# relays.net
KiCad netlist of a schematic drawn in Altium Designer
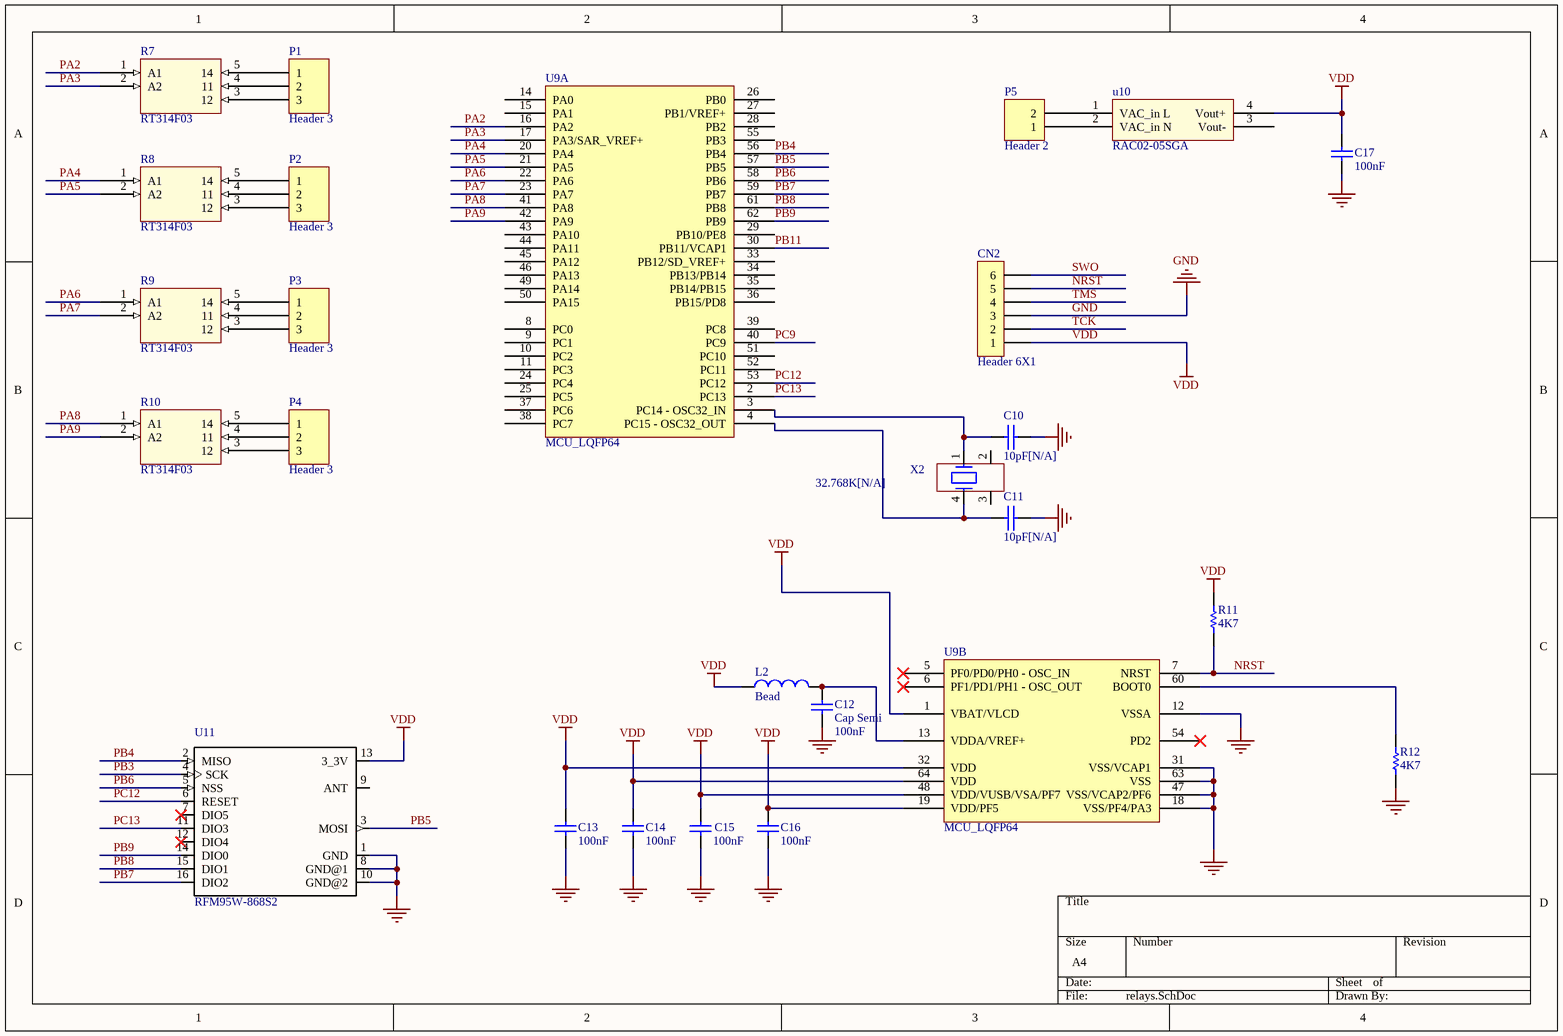
[diagram p0: relays.SchDoc]

(export (version "E")
  (design (tool "Eeschema 10.0.6"))
  (components
    (comp (ref "C10")
      (value "10pF[N/A]")
      (footprint "0603C")
      (description "Capacitor")
      (libsource (lib "MB1136") (part "CAP"))
    )
    (comp (ref "C11")
      (value "10pF[N/A]")
      (footprint "0603C")
      (description "Capacitor")
      (libsource (lib "*") (part "CAP"))
    )
    (comp (ref "C12")
      (value "Cap Semi")
      (footprint "1608[0603]")
      (description "Capacitor (Semiconductor SIM Model)")
      (fields (field (name "ALTIUM_VALUE") "100nF") (field (name "PUBLISHER") "Altium Limited"))
      (libsource (lib "Miscellaneous Devices") (part "Cap Semi"))
    )
    (comp (ref "C13")
      (value "100nF")
      (footprint "0603C")
      (description "Capacitor")
      (fields (field (name "PUBLISHER") "Altium Limited"))
      (libsource (lib "Miscellaneous Devices") (part "Cap"))
    )
    (comp (ref "C14")
      (value "100nF")
      (footprint "0603C")
      (description "Capacitor")
      (fields (field (name "PUBLISHER") "Altium Limited"))
      (libsource (lib "Miscellaneous Devices") (part "Cap"))
    )
    (comp (ref "C15")
      (value "100nF")
      (footprint "0603C")
      (description "Capacitor")
      (fields (field (name "PUBLISHER") "Altium Limited"))
      (libsource (lib "Miscellaneous Devices") (part "Cap"))
    )
    (comp (ref "C16")
      (value "100nF")
      (footprint "0603C")
      (description "Capacitor")
      (fields (field (name "PUBLISHER") "Altium Limited"))
      (libsource (lib "Miscellaneous Devices") (part "Cap"))
    )
    (comp (ref "C17")
      (value "100nF")
      (footprint "0603C")
      (description "Capacitor")
      (fields (field (name "PUBLISHER") "Altium Limited"))
      (libsource (lib "Miscellaneous Devices") (part "Cap"))
    )
    (comp (ref "CN2")
      (value "Header 6X1")
      (footprint "1*6P")
      (description "Header, 6-Pin, Single row")
      (fields (field (name "PUBLISHER") "Altium Limited"))
      (libsource (lib "MB1136") (part "Header 6X1"))
    )
    (comp (ref "L2")
      (value "Bead")
      (footprint "INDC1608L")
      (description "Inductor")
      (fields (field (name "PUBLISHER") "Altium Limited"))
      (libsource (lib "Miscellaneous Devices") (part "Inductor"))
    )
    (comp (ref "P1")
      (value "Header 3")
      (footprint "HDR1X3")
      (description "Header, 3-Pin")
      (fields (field (name "PUBLISHER") "Altium Limited"))
      (libsource (lib "Miscellaneous Connectors") (part "Header 3"))
    )
    (comp (ref "P2")
      (value "Header 3")
      (footprint "HDR1X3")
      (description "Header, 3-Pin")
      (fields (field (name "PUBLISHER") "Altium Limited"))
      (libsource (lib "Miscellaneous Connectors") (part "Header 3"))
    )
    (comp (ref "P3")
      (value "Header 3")
      (footprint "HDR1X3")
      (description "Header, 3-Pin")
      (fields (field (name "PUBLISHER") "Altium Limited"))
      (libsource (lib "Miscellaneous Connectors") (part "Header 3"))
    )
    (comp (ref "P4")
      (value "Header 3")
      (footprint "HDR1X3")
      (description "Header, 3-Pin")
      (fields (field (name "PUBLISHER") "Altium Limited"))
      (libsource (lib "Miscellaneous Connectors") (part "Header 3"))
    )
    (comp (ref "P5")
      (value "Header 2")
      (footprint "HDR1X2")
      (description "Header, 2-Pin")
      (fields (field (name "PUBLISHER") "Altium Limited"))
      (libsource (lib "Miscellaneous Connectors") (part "Header 2"))
    )
    (comp (ref "R7")
      (value "RT314F03")
      (footprint "RT314F03")
      (description "Latching relay")
      (libsource (lib "seeds") (part "RT314F03"))
    )
    (comp (ref "R8")
      (value "RT314F03")
      (footprint "RT314F03")
      (description "Latching relay")
      (libsource (lib "seeds") (part "RT314F03"))
    )
    (comp (ref "R9")
      (value "RT314F03")
      (footprint "RT314F03")
      (description "Latching relay")
      (libsource (lib "seeds") (part "RT314F03"))
    )
    (comp (ref "R10")
      (value "RT314F03")
      (footprint "RT314F03")
      (description "Latching relay")
      (libsource (lib "seeds") (part "RT314F03"))
    )
    (comp (ref "R11")
      (value "4K7")
      (footprint "0603R")
      (description "Resistor")
      (fields (field (name "PUBLISHER") "Altium Limited"))
      (libsource (lib "MB1136") (part "Res1"))
    )
    (comp (ref "R12")
      (value "4K7")
      (footprint "0603R")
      (description "Resistor")
      (fields (field (name "PUBLISHER") "Altium Limited"))
      (libsource (lib "MB1136") (part "Res1"))
    )
    (comp (ref "U9") (value "MCU_LQFP64") (footprint "LQFP64") (libsource (lib "MB1136") (part "MCU_LQFP64")))
    (comp (ref "u10")
      (value "RAC02-05SGA")
      (description "AC/DC converter")
      (libsource (lib "seeds") (part "RAC02-05SGA"))
    )
    (comp (ref "U11")
      (value "RFM95W-868S2")
      (footprint "XCVR_RFM95W-868S2")
      (fields (field (name "MF") "Hope Microelectronics"))
      (libsource (lib "RFM95W-868S2") (part "RFM95W-868S2"))
    )
    (comp (ref "X2") (value "32.768K[N/A]") (footprint "XTAL_4SM_8X3R8") (libsource (lib "*") (part "MC306")))
  )
  (nets
    (net (code "1") (name "/NRST") (class "Default")
      (node (ref "CN2") (pin "5") (pinfunction "5_5") (pintype "passive"))
      (node (ref "R11") (pin "1") (pinfunction "1_1") (pintype "passive"))
      (node (ref "U9") (pin "7") (pinfunction "NRST_7") (pintype "passive"))
    )
    (net (code "2") (name "/PA2") (class "Default")
      (node (ref "R7") (pin "1") (pinfunction "A1_1") (pintype "input"))
      (node (ref "U9") (pin "16") (pinfunction "PA2_16") (pintype "passive"))
    )
    (net (code "3") (name "/PA3") (class "Default")
      (node (ref "R7") (pin "2") (pinfunction "A2_2") (pintype "input"))
      (node (ref "U9") (pin "17") (pinfunction "PA3/SAR_VREF+_17") (pintype "passive"))
    )
    (net (code "4") (name "/PA4") (class "Default")
      (node (ref "R8") (pin "1") (pinfunction "A1_1") (pintype "input"))
      (node (ref "U9") (pin "20") (pinfunction "PA4_20") (pintype "passive"))
    )
    (net (code "5") (name "/PA5") (class "Default")
      (node (ref "R8") (pin "2") (pinfunction "A2_2") (pintype "input"))
      (node (ref "U9") (pin "21") (pinfunction "PA5_21") (pintype "passive"))
    )
    (net (code "6") (name "/PA6") (class "Default")
      (node (ref "R9") (pin "1") (pinfunction "A1_1") (pintype "input"))
      (node (ref "U9") (pin "22") (pinfunction "PA6_22") (pintype "passive"))
    )
    (net (code "7") (name "/PA7") (class "Default")
      (node (ref "R9") (pin "2") (pinfunction "A2_2") (pintype "input"))
      (node (ref "U9") (pin "23") (pinfunction "PA7_23") (pintype "passive"))
    )
    (net (code "8") (name "/PA8") (class "Default")
      (node (ref "R10") (pin "1") (pinfunction "A1_1") (pintype "input"))
      (node (ref "U9") (pin "41") (pinfunction "PA8_41") (pintype "passive"))
    )
    (net (code "9") (name "/PA9") (class "Default")
      (node (ref "R10") (pin "2") (pinfunction "A2_2") (pintype "input"))
      (node (ref "U9") (pin "42") (pinfunction "PA9_42") (pintype "passive"))
    )
    (net (code "10") (name "/PB3") (class "Default")
      (node (ref "U11") (pin "4") (pinfunction "SCK_4") (pintype "input"))
    )
    (net (code "11") (name "/PB4") (class "Default")
      (node (ref "U11") (pin "2") (pinfunction "MISO_2") (pintype "input"))
      (node (ref "U9") (pin "56") (pinfunction "PB4_56") (pintype "passive"))
    )
    (net (code "12") (name "/PB5") (class "Default")
      (node (ref "U11") (pin "3") (pinfunction "MOSI_3") (pintype "output"))
      (node (ref "U9") (pin "57") (pinfunction "PB5_57") (pintype "passive"))
    )
    (net (code "13") (name "/PB6") (class "Default")
      (node (ref "U11") (pin "5") (pinfunction "NSS_5") (pintype "input"))
      (node (ref "U9") (pin "58") (pinfunction "PB6_58") (pintype "passive"))
    )
    (net (code "14") (name "/PB7") (class "Default")
      (node (ref "U11") (pin "16") (pinfunction "DIO2_16") (pintype "bidirectional"))
      (node (ref "U9") (pin "59") (pinfunction "PB7_59") (pintype "passive"))
    )
    (net (code "15") (name "/PB8") (class "Default")
      (node (ref "U11") (pin "15") (pinfunction "DIO1_15") (pintype "bidirectional"))
      (node (ref "U9") (pin "61") (pinfunction "PB8_61") (pintype "passive"))
    )
    (net (code "16") (name "/PB9") (class "Default")
      (node (ref "U11") (pin "14") (pinfunction "DIO0_14") (pintype "bidirectional"))
      (node (ref "U9") (pin "62") (pinfunction "PB9_62") (pintype "passive"))
    )
    (net (code "17") (name "/PB11") (class "Default")
      (node (ref "U9") (pin "30") (pinfunction "PB11/VCAP1_30") (pintype "passive"))
    )
    (net (code "18") (name "/PC9") (class "Default")
      (node (ref "U9") (pin "40") (pinfunction "PC9_40") (pintype "passive"))
    )
    (net (code "19") (name "/PC12") (class "Default")
      (node (ref "U11") (pin "6") (pinfunction "RESET_6") (pintype "bidirectional"))
      (node (ref "U9") (pin "53") (pinfunction "PC12_53") (pintype "passive"))
    )
    (net (code "20") (name "/PC13") (class "Default")
      (node (ref "U11") (pin "11") (pinfunction "DIO3_11") (pintype "bidirectional"))
      (node (ref "U9") (pin "2") (pinfunction "PC13_2") (pintype "passive"))
    )
    (net (code "21") (name "/SWO") (class "Default")
      (node (ref "CN2") (pin "6") (pinfunction "6_6") (pintype "passive"))
    )
    (net (code "22") (name "/TCK") (class "Default")
      (node (ref "CN2") (pin "2") (pinfunction "2_2") (pintype "passive"))
    )
    (net (code "23") (name "/TMS") (class "Default")
      (node (ref "CN2") (pin "4") (pinfunction "4_4") (pintype "passive"))
    )
    (net (code "24") (name "GND") (class "Default")
      (node (ref "C10") (pin "2") (pinfunction "2_2") (pintype "passive"))
      (node (ref "C11") (pin "2") (pinfunction "2_2") (pintype "passive"))
      (node (ref "C12") (pin "2") (pinfunction "2_2") (pintype "passive"))
      (node (ref "C13") (pin "2") (pinfunction "2_2") (pintype "passive"))
      (node (ref "C14") (pin "2") (pinfunction "2_2") (pintype "passive"))
      (node (ref "C15") (pin "2") (pinfunction "2_2") (pintype "passive"))
      (node (ref "C16") (pin "2") (pinfunction "2_2") (pintype "passive"))
      (node (ref "C17") (pin "2") (pinfunction "2_2") (pintype "passive"))
      (node (ref "CN2") (pin "3") (pinfunction "3_3") (pintype "passive"))
      (node (ref "R12") (pin "1") (pinfunction "1_1") (pintype "passive"))
      (node (ref "U11") (pin "1") (pinfunction "GND_1") (pintype "power_in"))
      (node (ref "U11") (pin "10") (pinfunction "GND@2_10") (pintype "power_in"))
      (node (ref "U11") (pin "8") (pinfunction "GND@1_8") (pintype "power_in"))
      (node (ref "U9") (pin "12") (pinfunction "VSSA_12") (pintype "passive"))
      (node (ref "U9") (pin "18") (pinfunction "VSS/PF4/PA3_18") (pintype "passive"))
      (node (ref "U9") (pin "31") (pinfunction "VSS/VCAP1_31") (pintype "passive"))
      (node (ref "U9") (pin "47") (pinfunction "VSS/VCAP2/PF6_47") (pintype "passive"))
      (node (ref "U9") (pin "63") (pinfunction "VSS_63") (pintype "passive"))
    )
    (net (code "25") (name "Net-(R7-11)") (class "Default")
      (node (ref "P1") (pin "2") (pinfunction "2_2") (pintype "passive"))
      (node (ref "R7") (pin "4") (pinfunction "11_4") (pintype "input"))
    )
    (net (code "26") (name "Net-(R7-12)") (class "Default")
      (node (ref "P1") (pin "3") (pinfunction "3_3") (pintype "passive"))
      (node (ref "R7") (pin "3") (pinfunction "12_3") (pintype "input"))
    )
    (net (code "27") (name "Net-(R7-14)") (class "Default")
      (node (ref "P1") (pin "1") (pinfunction "1_1") (pintype "passive"))
      (node (ref "R7") (pin "5") (pinfunction "14_5") (pintype "input"))
    )
    (net (code "28") (name "Net-(R8-11)") (class "Default")
      (node (ref "P2") (pin "2") (pinfunction "2_2") (pintype "passive"))
      (node (ref "R8") (pin "4") (pinfunction "11_4") (pintype "input"))
    )
    (net (code "29") (name "Net-(R8-12)") (class "Default")
      (node (ref "P2") (pin "3") (pinfunction "3_3") (pintype "passive"))
      (node (ref "R8") (pin "3") (pinfunction "12_3") (pintype "input"))
    )
    (net (code "30") (name "Net-(R8-14)") (class "Default")
      (node (ref "P2") (pin "1") (pinfunction "1_1") (pintype "passive"))
      (node (ref "R8") (pin "5") (pinfunction "14_5") (pintype "input"))
    )
    (net (code "31") (name "Net-(R9-11)") (class "Default")
      (node (ref "P3") (pin "2") (pinfunction "2_2") (pintype "passive"))
      (node (ref "R9") (pin "4") (pinfunction "11_4") (pintype "input"))
    )
    (net (code "32") (name "Net-(R9-12)") (class "Default")
      (node (ref "P3") (pin "3") (pinfunction "3_3") (pintype "passive"))
      (node (ref "R9") (pin "3") (pinfunction "12_3") (pintype "input"))
    )
    (net (code "33") (name "Net-(R9-14)") (class "Default")
      (node (ref "P3") (pin "1") (pinfunction "1_1") (pintype "passive"))
      (node (ref "R9") (pin "5") (pinfunction "14_5") (pintype "input"))
    )
    (net (code "34") (name "Net-(R10-11)") (class "Default")
      (node (ref "P4") (pin "2") (pinfunction "2_2") (pintype "passive"))
      (node (ref "R10") (pin "4") (pinfunction "11_4") (pintype "input"))
    )
    (net (code "35") (name "Net-(R10-12)") (class "Default")
      (node (ref "P4") (pin "3") (pinfunction "3_3") (pintype "passive"))
      (node (ref "R10") (pin "3") (pinfunction "12_3") (pintype "input"))
    )
    (net (code "36") (name "Net-(R10-14)") (class "Default")
      (node (ref "P4") (pin "1") (pinfunction "1_1") (pintype "passive"))
      (node (ref "R10") (pin "5") (pinfunction "14_5") (pintype "input"))
    )
    (net (code "37") (name "Net-(U9A-PC14_-_OSC32_IN)") (class "Default")
      (node (ref "C10") (pin "1") (pinfunction "1_1") (pintype "passive"))
      (node (ref "U9") (pin "3") (pinfunction "PC14_-_OSC32_IN_3") (pintype "passive"))
      (node (ref "X2") (pin "1") (pinfunction "1_1") (pintype "passive"))
    )
    (net (code "38") (name "Net-(U9A-PC15_-_OSC32_OUT)") (class "Default")
      (node (ref "C11") (pin "1") (pinfunction "1_1") (pintype "passive"))
      (node (ref "U9") (pin "4") (pinfunction "PC15_-_OSC32_OUT_4") (pintype "passive"))
      (node (ref "X2") (pin "4") (pinfunction "4_4") (pintype "passive"))
    )
    (net (code "39") (name "Net-(U9B-BOOT0)") (class "Default")
      (node (ref "R12") (pin "2") (pinfunction "2_2") (pintype "passive"))
      (node (ref "U9") (pin "60") (pinfunction "BOOT0_60") (pintype "passive"))
    )
    (net (code "40") (name "Net-(U9B-VDDA{slash}VREF+)") (class "Default")
      (node (ref "C12") (pin "1") (pinfunction "1_1") (pintype "passive"))
      (node (ref "L2") (pin "2") (pinfunction "2_2") (pintype "passive"))
      (node (ref "U9") (pin "13") (pinfunction "VDDA/VREF+_13") (pintype "passive"))
    )
    (net (code "41") (name "Net-(u10-VAC_in_L)") (class "Default")
      (node (ref "P5") (pin "2") (pinfunction "2_2") (pintype "passive"))
      (node (ref "u10") (pin "1") (pinfunction "VAC_in_L_1") (pintype "power_in"))
    )
    (net (code "42") (name "Net-(u10-VAC_in_N)") (class "Default")
      (node (ref "P5") (pin "1") (pinfunction "1_1") (pintype "passive"))
      (node (ref "u10") (pin "2") (pinfunction "VAC_in_N_2") (pintype "power_in"))
    )
    (net (code "43") (name "VDD") (class "Default")
      (node (ref "C13") (pin "1") (pinfunction "1_1") (pintype "passive"))
      (node (ref "C14") (pin "1") (pinfunction "1_1") (pintype "passive"))
      (node (ref "C15") (pin "1") (pinfunction "1_1") (pintype "passive"))
      (node (ref "C16") (pin "1") (pinfunction "1_1") (pintype "passive"))
      (node (ref "C17") (pin "1") (pinfunction "1_1") (pintype "passive"))
      (node (ref "CN2") (pin "1") (pinfunction "1_1") (pintype "passive"))
      (node (ref "L2") (pin "1") (pinfunction "1_1") (pintype "passive"))
      (node (ref "R11") (pin "2") (pinfunction "2_2") (pintype "passive"))
      (node (ref "U11") (pin "13") (pinfunction "3_3V_13") (pintype "power_in"))
      (node (ref "U9") (pin "1") (pinfunction "VBAT/VLCD_1") (pintype "passive"))
      (node (ref "U9") (pin "19") (pinfunction "VDD/PF5_19") (pintype "passive"))
      (node (ref "U9") (pin "32") (pinfunction "VDD_32") (pintype "passive"))
      (node (ref "U9") (pin "48") (pinfunction "VDD/VUSB/VSA/PF7_48") (pintype "passive"))
      (node (ref "U9") (pin "64") (pinfunction "VDD_64") (pintype "passive"))
      (node (ref "u10") (pin "4") (pinfunction "Vout+_4") (pintype "power_in"))
    )
    (net (code "44") (name "unconnected-(U9A-PA0-Pad14)") (class "Default")
      (node (ref "U9") (pin "14") (pinfunction "PA0_14") (pintype "passive"))
    )
    (net (code "45") (name "unconnected-(U9A-PA1-Pad15)") (class "Default")
      (node (ref "U9") (pin "15") (pinfunction "PA1_15") (pintype "passive"))
    )
    (net (code "46") (name "unconnected-(U9A-PA10-Pad43)") (class "Default")
      (node (ref "U9") (pin "43") (pinfunction "PA10_43") (pintype "passive"))
    )
    (net (code "47") (name "unconnected-(U9A-PA11-Pad44)") (class "Default")
      (node (ref "U9") (pin "44") (pinfunction "PA11_44") (pintype "passive"))
    )
    (net (code "48") (name "unconnected-(U9A-PA12-Pad45)") (class "Default")
      (node (ref "U9") (pin "45") (pinfunction "PA12_45") (pintype "passive"))
    )
    (net (code "49") (name "unconnected-(U9A-PA13-Pad46)") (class "Default")
      (node (ref "U9") (pin "46") (pinfunction "PA13_46") (pintype "passive"))
    )
    (net (code "50") (name "unconnected-(U9A-PA14-Pad49)") (class "Default")
      (node (ref "U9") (pin "49") (pinfunction "PA14_49") (pintype "passive"))
    )
    (net (code "51") (name "unconnected-(U9A-PA15-Pad50)") (class "Default")
      (node (ref "U9") (pin "50") (pinfunction "PA15_50") (pintype "passive"))
    )
    (net (code "52") (name "unconnected-(U9A-PB0-Pad26)") (class "Default")
      (node (ref "U9") (pin "26") (pinfunction "PB0_26") (pintype "passive"))
    )
    (net (code "53") (name "unconnected-(U9A-PB1{slash}VREF+-Pad27)") (class "Default")
      (node (ref "U9") (pin "27") (pinfunction "PB1/VREF+_27") (pintype "passive"))
    )
    (net (code "54") (name "unconnected-(U9A-PB2-Pad28)") (class "Default")
      (node (ref "U9") (pin "28") (pinfunction "PB2_28") (pintype "passive"))
    )
    (net (code "55") (name "unconnected-(U9A-PB3-Pad55)") (class "Default")
      (node (ref "U9") (pin "55") (pinfunction "PB3_55") (pintype "passive"))
    )
    (net (code "56") (name "unconnected-(U9A-PB10{slash}PE8-Pad29)") (class "Default")
      (node (ref "U9") (pin "29") (pinfunction "PB10/PE8_29") (pintype "passive"))
    )
    (net (code "57") (name "unconnected-(U9A-PB12{slash}SD_VREF+-Pad33)") (class "Default")
      (node (ref "U9") (pin "33") (pinfunction "PB12/SD_VREF+_33") (pintype "passive"))
    )
    (net (code "58") (name "unconnected-(U9A-PB13{slash}PB14-Pad34)") (class "Default")
      (node (ref "U9") (pin "34") (pinfunction "PB13/PB14_34") (pintype "passive"))
    )
    (net (code "59") (name "unconnected-(U9A-PB14{slash}PB15-Pad35)") (class "Default")
      (node (ref "U9") (pin "35") (pinfunction "PB14/PB15_35") (pintype "passive"))
    )
    (net (code "60") (name "unconnected-(U9A-PB15{slash}PD8-Pad36)") (class "Default")
      (node (ref "U9") (pin "36") (pinfunction "PB15/PD8_36") (pintype "passive"))
    )
    (net (code "61") (name "unconnected-(U9A-PC0-Pad8)") (class "Default")
      (node (ref "U9") (pin "8") (pinfunction "PC0_8") (pintype "passive"))
    )
    (net (code "62") (name "unconnected-(U9A-PC1-Pad9)") (class "Default")
      (node (ref "U9") (pin "9") (pinfunction "PC1_9") (pintype "passive"))
    )
    (net (code "63") (name "unconnected-(U9A-PC2-Pad10)") (class "Default")
      (node (ref "U9") (pin "10") (pinfunction "PC2_10") (pintype "passive"))
    )
    (net (code "64") (name "unconnected-(U9A-PC3-Pad11)") (class "Default")
      (node (ref "U9") (pin "11") (pinfunction "PC3_11") (pintype "passive"))
    )
    (net (code "65") (name "unconnected-(U9A-PC4-Pad24)") (class "Default")
      (node (ref "U9") (pin "24") (pinfunction "PC4_24") (pintype "passive"))
    )
    (net (code "66") (name "unconnected-(U9A-PC5-Pad25)") (class "Default")
      (node (ref "U9") (pin "25") (pinfunction "PC5_25") (pintype "passive"))
    )
    (net (code "67") (name "unconnected-(U9A-PC6-Pad37)") (class "Default")
      (node (ref "U9") (pin "37") (pinfunction "PC6_37") (pintype "passive"))
    )
    (net (code "68") (name "unconnected-(U9A-PC7-Pad38)") (class "Default")
      (node (ref "U9") (pin "38") (pinfunction "PC7_38") (pintype "passive"))
    )
    (net (code "69") (name "unconnected-(U9A-PC8-Pad39)") (class "Default")
      (node (ref "U9") (pin "39") (pinfunction "PC8_39") (pintype "passive"))
    )
    (net (code "70") (name "unconnected-(U9A-PC10-Pad51)") (class "Default")
      (node (ref "U9") (pin "51") (pinfunction "PC10_51") (pintype "passive"))
    )
    (net (code "71") (name "unconnected-(U9A-PC11-Pad52)") (class "Default")
      (node (ref "U9") (pin "52") (pinfunction "PC11_52") (pintype "passive"))
    )
    (net (code "72") (name "unconnected-(U9B-PD2-Pad54)") (class "Default")
      (node (ref "U9") (pin "54") (pinfunction "PD2_54") (pintype "passive+no_connect"))
    )
    (net (code "73") (name "unconnected-(U9B-PF0{slash}PD0{slash}PH0_-_OSC_IN-Pad5)") (class "Default")
      (node (ref "U9") (pin "5") (pinfunction "PF0/PD0/PH0_-_OSC_IN_5") (pintype "passive+no_connect"))
    )
    (net (code "74") (name "unconnected-(U9B-PF1{slash}PD1{slash}PH1_-_OSC_OUT-Pad6)") (class "Default")
      (node (ref "U9") (pin "6") (pinfunction "PF1/PD1/PH1_-_OSC_OUT_6") (pintype "passive+no_connect"))
    )
    (net (code "75") (name "unconnected-(U11-ANT-Pad9)") (class "Default")
      (node (ref "U11") (pin "9") (pinfunction "ANT_9") (pintype "passive"))
    )
    (net (code "76") (name "unconnected-(U11-DIO4-Pad12)") (class "Default")
      (node (ref "U11") (pin "12") (pinfunction "DIO4_12") (pintype "bidirectional+no_connect"))
    )
    (net (code "77") (name "unconnected-(U11-DIO5-Pad7)") (class "Default")
      (node (ref "U11") (pin "7") (pinfunction "DIO5_7") (pintype "bidirectional+no_connect"))
    )
    (net (code "78") (name "unconnected-(X2-Pad2)") (class "Default")
      (node (ref "X2") (pin "2") (pinfunction "2_2") (pintype "passive"))
    )
    (net (code "79") (name "unconnected-(X2-Pad3)") (class "Default")
      (node (ref "X2") (pin "3") (pinfunction "3_3") (pintype "passive"))
    )
    (net (code "80") (name "unconnected-(u10-Vout--Pad3)") (class "Default")
      (node (ref "u10") (pin "3") (pinfunction "Vout-_3") (pintype "power_in"))
    )
  )
)
